# R2P_GW_module.net
KiCad netlist of a schematic drawn in EAGLE
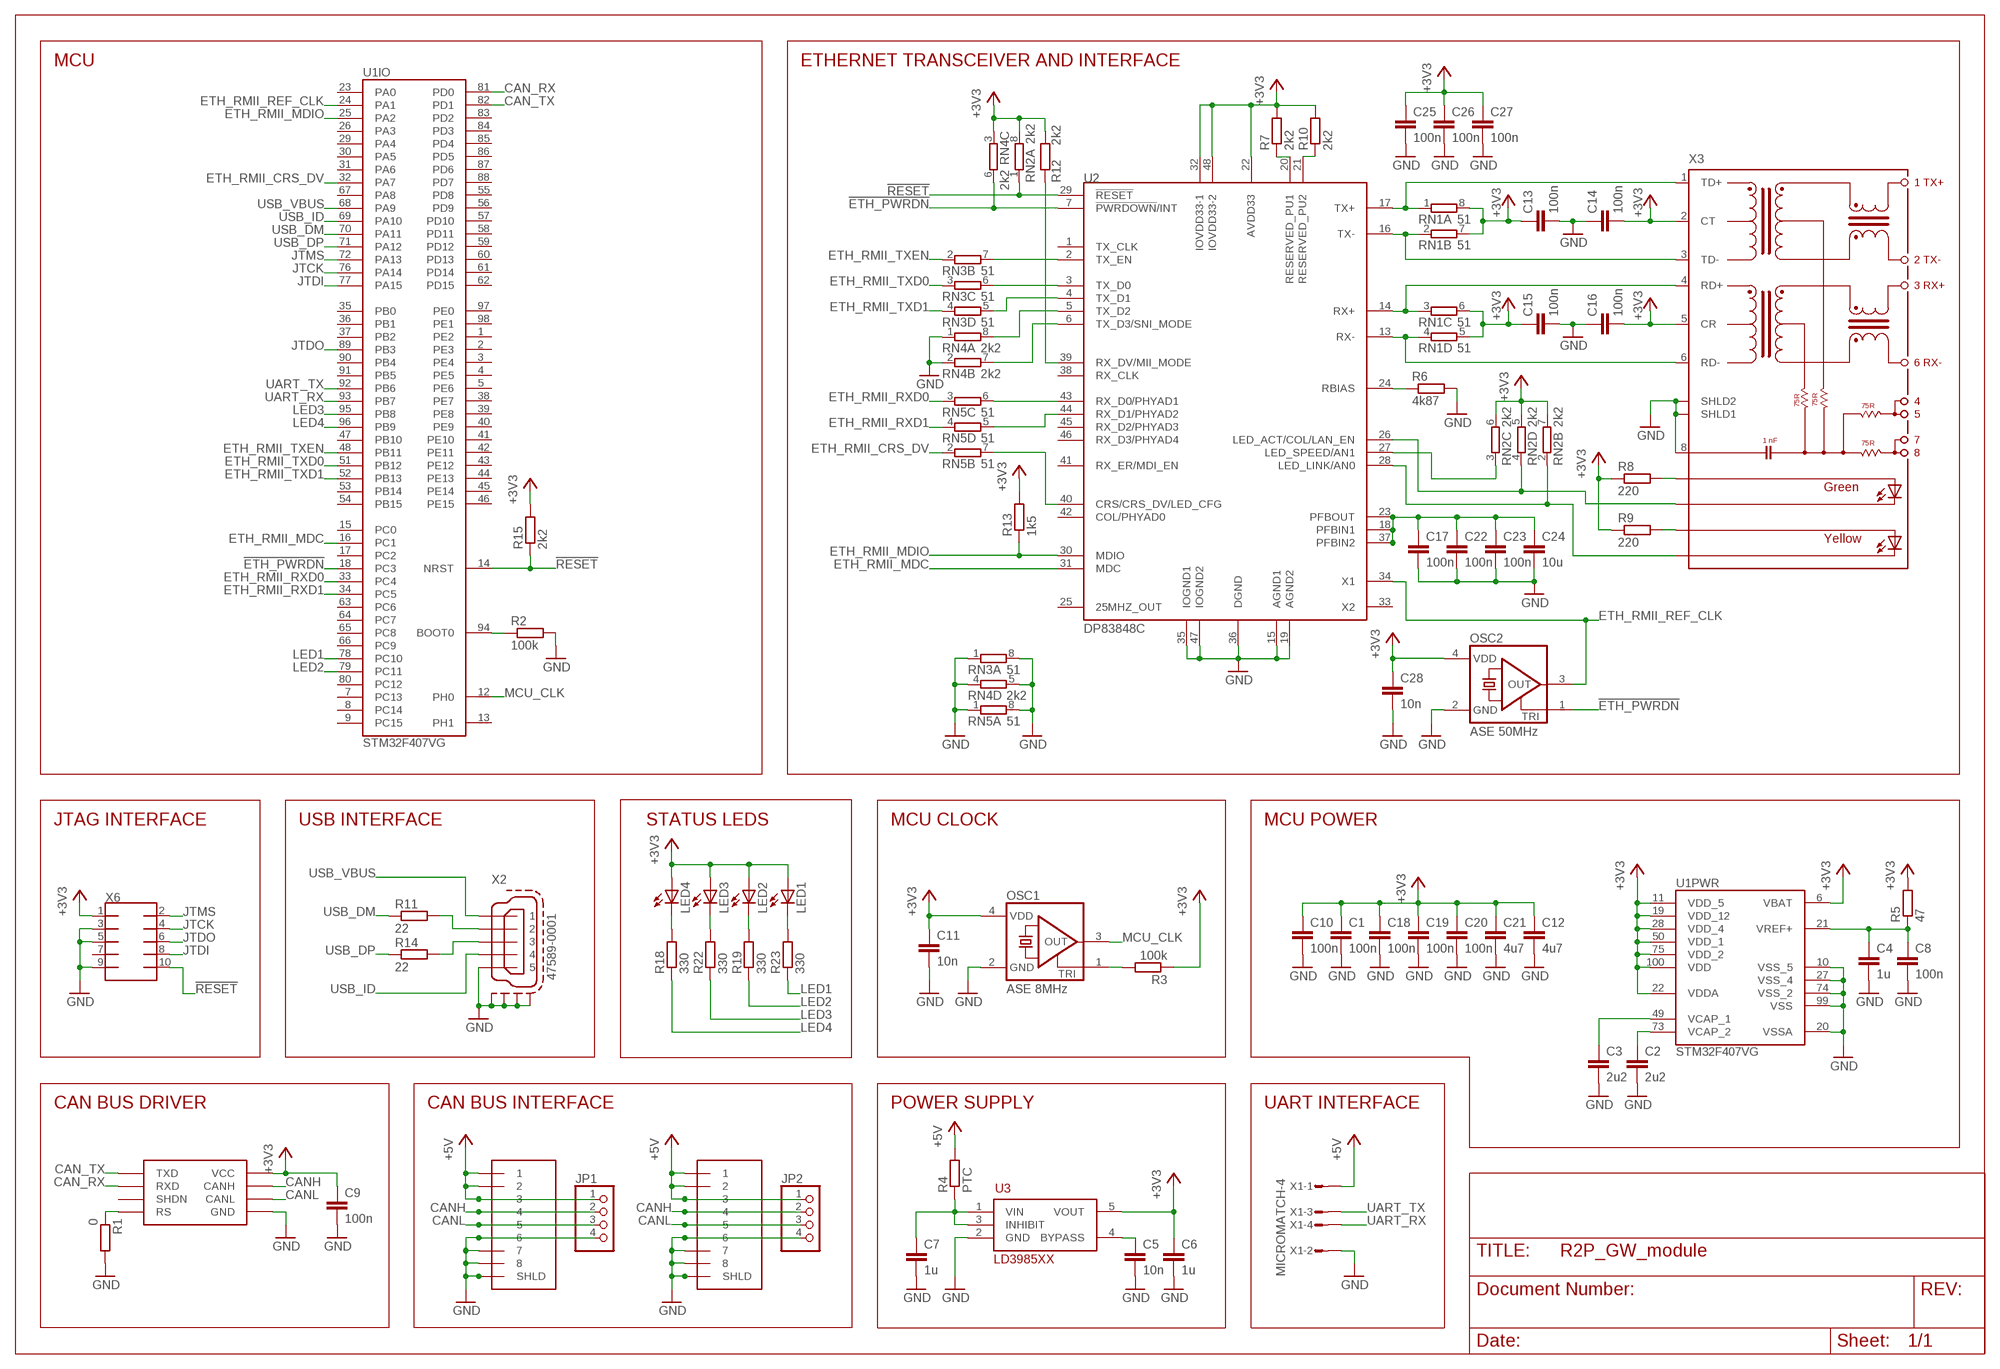
[diagram p0: schematic, sheet 1]

(export (version "E")
  (design (tool "Eeschema 10.0.6"))
  (components
    (comp (ref "C1")
      (value "100n")
      (footprint "eagle-import:C0603")
      (libsource (lib "eagle-import") (part "C-EUC0603"))
    )
    (comp (ref "C2")
      (value "2u2")
      (footprint "eagle-import:C0805")
      (libsource (lib "eagle-import") (part "C-EUC0805"))
    )
    (comp (ref "C3")
      (value "2u2")
      (footprint "eagle-import:C0805")
      (libsource (lib "eagle-import") (part "C-EUC0805"))
    )
    (comp (ref "C4")
      (value "1u")
      (footprint "eagle-import:C0603")
      (libsource (lib "eagle-import") (part "C-EUC0603"))
    )
    (comp (ref "C5")
      (value "10n")
      (footprint "eagle-import:C0603")
      (libsource (lib "eagle-import") (part "C-EUC0603"))
    )
    (comp (ref "C6")
      (value "1u")
      (footprint "eagle-import:C0603")
      (libsource (lib "eagle-import") (part "C-EUC0603"))
    )
    (comp (ref "C7")
      (value "1u")
      (footprint "eagle-import:C0603")
      (libsource (lib "eagle-import") (part "C-EUC0603"))
    )
    (comp (ref "C8")
      (value "100n")
      (footprint "eagle-import:C0603")
      (libsource (lib "eagle-import") (part "C-EUC0603"))
    )
    (comp (ref "C9")
      (value "100n")
      (footprint "eagle-import:C0603")
      (libsource (lib "eagle-import") (part "C-EUC0603"))
    )
    (comp (ref "C10")
      (value "100n")
      (footprint "eagle-import:C0603")
      (libsource (lib "eagle-import") (part "C-EUC0603"))
    )
    (comp (ref "C11")
      (value "10n")
      (footprint "eagle-import:C0603")
      (libsource (lib "eagle-import") (part "C-EUC0603"))
    )
    (comp (ref "C12")
      (value "4u7")
      (footprint "eagle-import:C0805")
      (libsource (lib "eagle-import") (part "C-EUC0805"))
    )
    (comp (ref "C13")
      (value "100n")
      (footprint "eagle-import:C0603")
      (libsource (lib "eagle-import") (part "C-EUC0603"))
    )
    (comp (ref "C14")
      (value "100n")
      (footprint "eagle-import:C0603")
      (libsource (lib "eagle-import") (part "C-EUC0603"))
    )
    (comp (ref "C15")
      (value "100n")
      (footprint "eagle-import:C0603")
      (libsource (lib "eagle-import") (part "C-EUC0603"))
    )
    (comp (ref "C16")
      (value "100n")
      (footprint "eagle-import:C0603")
      (libsource (lib "eagle-import") (part "C-EUC0603"))
    )
    (comp (ref "C17")
      (value "100n")
      (footprint "eagle-import:C0603")
      (libsource (lib "eagle-import") (part "C-EUC0603"))
    )
    (comp (ref "C18")
      (value "100n")
      (footprint "eagle-import:C0603")
      (libsource (lib "eagle-import") (part "C-EUC0603"))
    )
    (comp (ref "C19")
      (value "100n")
      (footprint "eagle-import:C0603")
      (libsource (lib "eagle-import") (part "C-EUC0603"))
    )
    (comp (ref "C20")
      (value "100n")
      (footprint "eagle-import:C0603")
      (libsource (lib "eagle-import") (part "C-EUC0603"))
    )
    (comp (ref "C21")
      (value "4u7")
      (footprint "eagle-import:C0805")
      (libsource (lib "eagle-import") (part "C-EUC0805"))
    )
    (comp (ref "C22")
      (value "100n")
      (footprint "eagle-import:C0603")
      (libsource (lib "eagle-import") (part "C-EUC0603"))
    )
    (comp (ref "C23")
      (value "100n")
      (footprint "eagle-import:C0603")
      (libsource (lib "eagle-import") (part "C-EUC0603"))
    )
    (comp (ref "C24")
      (value "10u")
      (footprint "eagle-import:C0805")
      (libsource (lib "eagle-import") (part "C-EUC0805"))
    )
    (comp (ref "C25")
      (value "100n")
      (footprint "eagle-import:C0603")
      (libsource (lib "eagle-import") (part "C-EUC0603"))
    )
    (comp (ref "C26")
      (value "100n")
      (footprint "eagle-import:C0603")
      (libsource (lib "eagle-import") (part "C-EUC0603"))
    )
    (comp (ref "C27")
      (value "100n")
      (footprint "eagle-import:C0603")
      (libsource (lib "eagle-import") (part "C-EUC0603"))
    )
    (comp (ref "C28")
      (value "10n")
      (footprint "eagle-import:C0603")
      (libsource (lib "eagle-import") (part "C-EUC0603"))
    )
    (comp (ref "JP1")
      (value "PINHD-1X4")
      (footprint "eagle-import:1X04")
      (libsource (lib "eagle-import") (part "PINHD-1X4"))
    )
    (comp (ref "JP2")
      (value "PINHD-1X4")
      (footprint "eagle-import:1X04")
      (libsource (lib "eagle-import") (part "PINHD-1X4"))
    )
    (comp (ref "LED1")
      (value "LEDCHIPLED_0805")
      (footprint "eagle-import:CHIPLED_0805")
      (libsource (lib "eagle-import") (part "LEDCHIPLED_0805"))
    )
    (comp (ref "LED2")
      (value "LEDCHIPLED_0805")
      (footprint "eagle-import:CHIPLED_0805")
      (libsource (lib "eagle-import") (part "LEDCHIPLED_0805"))
    )
    (comp (ref "LED3")
      (value "LEDCHIPLED_0805")
      (footprint "eagle-import:CHIPLED_0805")
      (libsource (lib "eagle-import") (part "LEDCHIPLED_0805"))
    )
    (comp (ref "LED4")
      (value "LEDCHIPLED_0805")
      (footprint "eagle-import:CHIPLED_0805")
      (libsource (lib "eagle-import") (part "LEDCHIPLED_0805"))
    )
    (comp (ref "OSC1")
      (value "ASE 8MHz")
      (footprint "eagle-import:ASE")
      (fields (field (name "OC_FARNELL") "unknown") (field (name "OC_NEWARK") "unknown"))
      (libsource (lib "eagle-import") (part "ASE"))
    )
    (comp (ref "OSC2")
      (value "ASE 50MHz")
      (footprint "eagle-import:ASE")
      (libsource (lib "eagle-import") (part "ASE"))
    )
    (comp (ref "R1")
      (value "0")
      (footprint "eagle-import:R0603")
      (libsource (lib "eagle-import") (part "R-EU_R0603"))
    )
    (comp (ref "R2")
      (value "100k")
      (footprint "eagle-import:R0603")
      (libsource (lib "eagle-import") (part "R-EU_R0603"))
    )
    (comp (ref "R3")
      (value "100k")
      (footprint "eagle-import:R0603")
      (libsource (lib "eagle-import") (part "R-EU_R0603"))
    )
    (comp (ref "R4")
      (value "PTC")
      (footprint "eagle-import:R0603")
      (libsource (lib "eagle-import") (part "R-EU_R0603"))
    )
    (comp (ref "R5")
      (value "47")
      (footprint "eagle-import:R0603")
      (libsource (lib "eagle-import") (part "R-EU_R0603"))
    )
    (comp (ref "R6")
      (value "4k87")
      (footprint "eagle-import:R0603")
      (libsource (lib "eagle-import") (part "R-EU_R0603"))
    )
    (comp (ref "R7")
      (value "2k2")
      (footprint "eagle-import:R0603")
      (libsource (lib "eagle-import") (part "R-EU_R0603"))
    )
    (comp (ref "R8")
      (value "220")
      (footprint "eagle-import:R0603")
      (libsource (lib "eagle-import") (part "R-EU_R0603"))
    )
    (comp (ref "R9")
      (value "220")
      (footprint "eagle-import:R0603")
      (libsource (lib "eagle-import") (part "R-EU_R0603"))
    )
    (comp (ref "R10")
      (value "2k2")
      (footprint "eagle-import:R0603")
      (libsource (lib "eagle-import") (part "R-EU_R0603"))
    )
    (comp (ref "R11")
      (value "22")
      (footprint "eagle-import:R0603")
      (libsource (lib "eagle-import") (part "R-EU_R0603"))
    )
    (comp (ref "R12")
      (value "2k2")
      (footprint "eagle-import:R0603")
      (libsource (lib "eagle-import") (part "R-EU_R0603"))
    )
    (comp (ref "R13")
      (value "1k5")
      (footprint "eagle-import:R0603")
      (libsource (lib "eagle-import") (part "R-EU_R0603"))
    )
    (comp (ref "R14")
      (value "22")
      (footprint "eagle-import:R0603")
      (libsource (lib "eagle-import") (part "R-EU_R0603"))
    )
    (comp (ref "R15")
      (value "2k2")
      (footprint "eagle-import:R0603")
      (libsource (lib "eagle-import") (part "R-EU_R0603"))
    )
    (comp (ref "R18")
      (value "330")
      (footprint "eagle-import:R0603")
      (libsource (lib "eagle-import") (part "R-EU_R0603"))
    )
    (comp (ref "R19")
      (value "330")
      (footprint "eagle-import:R0603")
      (libsource (lib "eagle-import") (part "R-EU_R0603"))
    )
    (comp (ref "R22")
      (value "330")
      (footprint "eagle-import:R0603")
      (libsource (lib "eagle-import") (part "R-EU_R0603"))
    )
    (comp (ref "R23")
      (value "330")
      (footprint "eagle-import:R0603")
      (libsource (lib "eagle-import") (part "R-EU_R0603"))
    )
    (comp (ref "RN1")
      (value "51")
      (footprint "eagle-import:CAT16")
      (libsource (lib "eagle-import") (part "4R-NCAT16"))
    )
    (comp (ref "RN2")
      (value "2k2")
      (footprint "eagle-import:CAT16")
      (libsource (lib "eagle-import") (part "4R-NCAT16"))
    )
    (comp (ref "RN3")
      (value "51")
      (footprint "eagle-import:CAT16")
      (libsource (lib "eagle-import") (part "4R-NCAT16"))
    )
    (comp (ref "RN4")
      (value "2k2")
      (footprint "eagle-import:CAT16")
      (libsource (lib "eagle-import") (part "4R-NCAT16"))
    )
    (comp (ref "RN5")
      (value "51")
      (footprint "eagle-import:CAT16")
      (libsource (lib "eagle-import") (part "4R-NCAT16"))
    )
    (comp (ref "U1")
      (value "STM32F407VG")
      (footprint "eagle-import:LQFP100")
      (libsource (lib "eagle-import") (part "STM32F407VG"))
    )
    (comp (ref "U2")
      (value "DP83848C")
      (footprint "eagle-import:LQFP48")
      (libsource (lib "eagle-import") (part "DP83848C"))
    )
    (comp (ref "U3")
      (value "LD3985XX")
      (footprint "eagle-import:SOT23-5L")
      (libsource (lib "eagle-import") (part "LD3985XX"))
    )
    (comp (ref "U4")
      (value "MAX3051")
      (footprint "eagle-import:SOT23-8L")
      (libsource (lib "eagle-import") (part "MAX3051"))
    )
    (comp (ref "X1")
      (value "MICROMATCH-4")
      (footprint "eagle-import:MICROMATCH-4")
      (libsource (lib "eagle-import") (part "MICROMATCH-4"))
    )
    (comp (ref "X2")
      (value "47589-0001")
      (footprint "eagle-import:47589-0001")
      (libsource (lib "eagle-import") (part "47589-0001"))
    )
    (comp (ref "X3")
      (value "SI-60062-F")
      (footprint "eagle-import:SI-60062-F")
      (libsource (lib "eagle-import") (part "SI-60062-F"))
    )
    (comp (ref "X4")
      (value "RJ45-43860")
      (footprint "eagle-import:0438600010")
      (libsource (lib "eagle-import") (part "RJ45-43860"))
    )
    (comp (ref "X5")
      (value "RJ45-43860")
      (footprint "eagle-import:0438600010")
      (libsource (lib "eagle-import") (part "RJ45-43860"))
    )
    (comp (ref "X6")
      (value "FTSH-105")
      (footprint "eagle-import:FTSH-105")
      (libsource (lib "eagle-import") (part "FTSH-105"))
    )
  )
  (nets
    (net (code "1") (name "+3V3") (class "Default")
      (node (ref "C1") (pin "1") (pinfunction "1_1") (pintype "passive"))
      (node (ref "C10") (pin "1") (pinfunction "1_1") (pintype "passive"))
      (node (ref "C11") (pin "1") (pinfunction "1_1") (pintype "passive"))
      (node (ref "C12") (pin "1") (pinfunction "1_1") (pintype "passive"))
      (node (ref "C13") (pin "1") (pinfunction "1_1") (pintype "passive"))
      (node (ref "C14") (pin "2") (pinfunction "2_2") (pintype "passive"))
      (node (ref "C15") (pin "1") (pinfunction "1_1") (pintype "passive"))
      (node (ref "C16") (pin "2") (pinfunction "2_2") (pintype "passive"))
      (node (ref "C18") (pin "1") (pinfunction "1_1") (pintype "passive"))
      (node (ref "C19") (pin "1") (pinfunction "1_1") (pintype "passive"))
      (node (ref "C20") (pin "1") (pinfunction "1_1") (pintype "passive"))
      (node (ref "C21") (pin "1") (pinfunction "1_1") (pintype "passive"))
      (node (ref "C25") (pin "1") (pinfunction "1_1") (pintype "passive"))
      (node (ref "C26") (pin "1") (pinfunction "1_1") (pintype "passive"))
      (node (ref "C27") (pin "1") (pinfunction "1_1") (pintype "passive"))
      (node (ref "C28") (pin "1") (pinfunction "1_1") (pintype "passive"))
      (node (ref "C6") (pin "1") (pinfunction "1_1") (pintype "passive"))
      (node (ref "C9") (pin "1") (pinfunction "1_1") (pintype "passive"))
      (node (ref "LED1") (pin "A") (pinfunction "A_A") (pintype "passive"))
      (node (ref "LED2") (pin "A") (pinfunction "A_A") (pintype "passive"))
      (node (ref "LED3") (pin "A") (pinfunction "A_A") (pintype "passive"))
      (node (ref "LED4") (pin "A") (pinfunction "A_A") (pintype "passive"))
      (node (ref "OSC1") (pin "4") (pinfunction "VDD_4") (pintype "power_in"))
      (node (ref "OSC2") (pin "4") (pinfunction "VDD_4") (pintype "power_in"))
      (node (ref "R10") (pin "2") (pinfunction "2_2") (pintype "passive"))
      (node (ref "R12") (pin "2") (pinfunction "2_2") (pintype "passive"))
      (node (ref "R13") (pin "2") (pinfunction "2_2") (pintype "passive"))
      (node (ref "R15") (pin "2") (pinfunction "2_2") (pintype "passive"))
      (node (ref "R3") (pin "1") (pinfunction "1_1") (pintype "passive"))
      (node (ref "R5") (pin "2") (pinfunction "2_2") (pintype "passive"))
      (node (ref "R7") (pin "2") (pinfunction "2_2") (pintype "passive"))
      (node (ref "R8") (pin "1") (pinfunction "1_1") (pintype "passive"))
      (node (ref "R9") (pin "1") (pinfunction "1_1") (pintype "passive"))
      (node (ref "RN1") (pin "5") (pinfunction "2_5") (pintype "passive"))
      (node (ref "RN1") (pin "6") (pinfunction "2_6") (pintype "passive"))
      (node (ref "RN1") (pin "7") (pinfunction "2_7") (pintype "passive"))
      (node (ref "RN1") (pin "8") (pinfunction "2_8") (pintype "passive"))
      (node (ref "RN2") (pin "5") (pinfunction "2_5") (pintype "passive"))
      (node (ref "RN2") (pin "6") (pinfunction "2_6") (pintype "passive"))
      (node (ref "RN2") (pin "7") (pinfunction "2_7") (pintype "passive"))
      (node (ref "RN2") (pin "8") (pinfunction "2_8") (pintype "passive"))
      (node (ref "RN4") (pin "3") (pinfunction "1_3") (pintype "passive"))
      (node (ref "U1") (pin "100") (pinfunction "VDD_100") (pintype "power_in"))
      (node (ref "U1") (pin "11") (pinfunction "VDD_5_11") (pintype "power_in"))
      (node (ref "U1") (pin "19") (pinfunction "VDD_12_19") (pintype "power_in"))
      (node (ref "U1") (pin "22") (pinfunction "VDDA_22") (pintype "power_in"))
      (node (ref "U1") (pin "28") (pinfunction "VDD_4_28") (pintype "power_in"))
      (node (ref "U1") (pin "50") (pinfunction "VDD_1_50") (pintype "power_in"))
      (node (ref "U1") (pin "6") (pinfunction "VBAT_6") (pintype "power_in"))
      (node (ref "U1") (pin "75") (pinfunction "VDD_2_75") (pintype "power_in"))
      (node (ref "U2") (pin "22") (pinfunction "AVDD33_22") (pintype "bidirectional"))
      (node (ref "U2") (pin "32") (pinfunction "IOVDD33-1_32") (pintype "bidirectional"))
      (node (ref "U2") (pin "48") (pinfunction "IOVDD33-2_48") (pintype "bidirectional"))
      (node (ref "U3") (pin "5") (pinfunction "VOUT_5") (pintype "bidirectional"))
      (node (ref "U4") (pin "P$3") (pinfunction "VCC_P$3") (pintype "bidirectional"))
      (node (ref "X3") (pin "2") (pinfunction "CT_2") (pintype "passive"))
      (node (ref "X3") (pin "5") (pinfunction "CR_5") (pintype "passive"))
      (node (ref "X6") (pin "1") (pinfunction "1_1") (pintype "passive"))
    )
    (net (code "2") (name "+5V") (class "Default")
      (node (ref "JP1") (pin "1") (pinfunction "1_1") (pintype "passive"))
      (node (ref "JP2") (pin "1") (pinfunction "1_1") (pintype "passive"))
      (node (ref "R4") (pin "2") (pinfunction "2_2") (pintype "passive"))
      (node (ref "X1") (pin "1") (pinfunction "S_1") (pintype "passive"))
      (node (ref "X4") (pin "P$1") (pinfunction "1_P$1") (pintype "bidirectional"))
      (node (ref "X4") (pin "P$2") (pinfunction "2_P$2") (pintype "bidirectional"))
      (node (ref "X4") (pin "P$3") (pinfunction "3_P$3") (pintype "bidirectional"))
      (node (ref "X5") (pin "P$1") (pinfunction "1_P$1") (pintype "bidirectional"))
      (node (ref "X5") (pin "P$2") (pinfunction "2_P$2") (pintype "bidirectional"))
      (node (ref "X5") (pin "P$3") (pinfunction "3_P$3") (pintype "bidirectional"))
    )
    (net (code "3") (name "/CANH") (class "Default")
      (node (ref "JP1") (pin "2") (pinfunction "2_2") (pintype "passive"))
      (node (ref "JP2") (pin "2") (pinfunction "2_2") (pintype "passive"))
      (node (ref "U4") (pin "P$7") (pinfunction "CANH_P$7") (pintype "bidirectional"))
      (node (ref "X4") (pin "P$4") (pinfunction "4_P$4") (pintype "bidirectional"))
      (node (ref "X5") (pin "P$4") (pinfunction "4_P$4") (pintype "bidirectional"))
    )
    (net (code "4") (name "/CANL") (class "Default")
      (node (ref "JP1") (pin "3") (pinfunction "3_3") (pintype "passive"))
      (node (ref "JP2") (pin "3") (pinfunction "3_3") (pintype "passive"))
      (node (ref "U4") (pin "P$6") (pinfunction "CANL_P$6") (pintype "bidirectional"))
      (node (ref "X4") (pin "P$5") (pinfunction "5_P$5") (pintype "bidirectional"))
      (node (ref "X5") (pin "P$5") (pinfunction "5_P$5") (pintype "bidirectional"))
    )
    (net (code "5") (name "/CAN_RX") (class "Default")
      (node (ref "U1") (pin "81") (pinfunction "PD0_81") (pintype "passive"))
      (node (ref "U4") (pin "P$4") (pinfunction "RXD_P$4") (pintype "bidirectional"))
    )
    (net (code "6") (name "/CAN_TX") (class "Default")
      (node (ref "U1") (pin "82") (pinfunction "PD1_82") (pintype "passive"))
      (node (ref "U4") (pin "P$1") (pinfunction "TXD_P$1") (pintype "bidirectional"))
    )
    (net (code "7") (name "/ETH_RMII_CRS_DV") (class "Default")
      (node (ref "RN5") (pin "2") (pinfunction "1_2") (pintype "passive"))
      (node (ref "U1") (pin "32") (pinfunction "PA7_32") (pintype "passive"))
    )
    (net (code "8") (name "/ETH_RMII_MDC") (class "Default")
      (node (ref "U1") (pin "16") (pinfunction "PC1_16") (pintype "passive"))
      (node (ref "U2") (pin "31") (pinfunction "MDC_31") (pintype "bidirectional"))
    )
    (net (code "9") (name "/ETH_RMII_MDIO") (class "Default")
      (node (ref "R13") (pin "1") (pinfunction "1_1") (pintype "passive"))
      (node (ref "U1") (pin "25") (pinfunction "PA2_25") (pintype "passive"))
      (node (ref "U2") (pin "30") (pinfunction "MDIO_30") (pintype "bidirectional"))
    )
    (net (code "10") (name "/ETH_RMII_REF_CLK") (class "Default")
      (node (ref "OSC2") (pin "3") (pinfunction "OUT_3") (pintype "output"))
      (node (ref "U1") (pin "24") (pinfunction "PA1_24") (pintype "passive"))
      (node (ref "U2") (pin "34") (pinfunction "X1_34") (pintype "bidirectional"))
    )
    (net (code "11") (name "/ETH_RMII_RXD0") (class "Default")
      (node (ref "RN5") (pin "3") (pinfunction "1_3") (pintype "passive"))
      (node (ref "U1") (pin "33") (pinfunction "PC4_33") (pintype "passive"))
    )
    (net (code "12") (name "/ETH_RMII_RXD1") (class "Default")
      (node (ref "RN5") (pin "4") (pinfunction "1_4") (pintype "passive"))
      (node (ref "U1") (pin "34") (pinfunction "PC5_34") (pintype "passive"))
    )
    (net (code "13") (name "/ETH_RMII_TXD0") (class "Default")
      (node (ref "RN3") (pin "3") (pinfunction "1_3") (pintype "passive"))
      (node (ref "U1") (pin "51") (pinfunction "PB12_51") (pintype "passive"))
    )
    (net (code "14") (name "/ETH_RMII_TXD1") (class "Default")
      (node (ref "RN3") (pin "4") (pinfunction "1_4") (pintype "passive"))
      (node (ref "U1") (pin "52") (pinfunction "PB13_52") (pintype "passive"))
    )
    (net (code "15") (name "/ETH_RMII_TXEN") (class "Default")
      (node (ref "RN3") (pin "2") (pinfunction "1_2") (pintype "passive"))
      (node (ref "U1") (pin "48") (pinfunction "PB11_48") (pintype "passive"))
    )
    (net (code "16") (name "/JTCK") (class "Default")
      (node (ref "U1") (pin "76") (pinfunction "PA14_76") (pintype "passive"))
      (node (ref "X6") (pin "4") (pinfunction "4_4") (pintype "passive"))
    )
    (net (code "17") (name "/JTDI") (class "Default")
      (node (ref "U1") (pin "77") (pinfunction "PA15_77") (pintype "passive"))
      (node (ref "X6") (pin "8") (pinfunction "8_8") (pintype "passive"))
    )
    (net (code "18") (name "/JTDO") (class "Default")
      (node (ref "U1") (pin "89") (pinfunction "PB3_89") (pintype "passive"))
      (node (ref "X6") (pin "6") (pinfunction "6_6") (pintype "passive"))
    )
    (net (code "19") (name "/JTMS") (class "Default")
      (node (ref "U1") (pin "72") (pinfunction "PA13_72") (pintype "passive"))
      (node (ref "X6") (pin "2") (pinfunction "2_2") (pintype "passive"))
    )
    (net (code "20") (name "/LED1") (class "Default")
      (node (ref "R23") (pin "1") (pinfunction "1_1") (pintype "passive"))
      (node (ref "U1") (pin "78") (pinfunction "PC10_78") (pintype "passive"))
    )
    (net (code "21") (name "/LED2") (class "Default")
      (node (ref "R19") (pin "1") (pinfunction "1_1") (pintype "passive"))
      (node (ref "U1") (pin "79") (pinfunction "PC11_79") (pintype "passive"))
    )
    (net (code "22") (name "/LED3") (class "Default")
      (node (ref "R22") (pin "1") (pinfunction "1_1") (pintype "passive"))
      (node (ref "U1") (pin "95") (pinfunction "PB8_95") (pintype "passive"))
    )
    (net (code "23") (name "/LED4") (class "Default")
      (node (ref "R18") (pin "1") (pinfunction "1_1") (pintype "passive"))
      (node (ref "U1") (pin "96") (pinfunction "PB9_96") (pintype "passive"))
    )
    (net (code "24") (name "/MCU_CLK") (class "Default")
      (node (ref "OSC1") (pin "3") (pinfunction "OUT_3") (pintype "output"))
      (node (ref "U1") (pin "12") (pinfunction "PH0_12") (pintype "passive"))
    )
    (net (code "25") (name "/UART_RX") (class "Default")
      (node (ref "U1") (pin "93") (pinfunction "PB7_93") (pintype "passive"))
      (node (ref "X1") (pin "4") (pinfunction "S_4") (pintype "passive"))
    )
    (net (code "26") (name "/UART_TX") (class "Default")
      (node (ref "U1") (pin "92") (pinfunction "PB6_92") (pintype "passive"))
      (node (ref "X1") (pin "3") (pinfunction "S_3") (pintype "passive"))
    )
    (net (code "27") (name "/USB_DM") (class "Default")
      (node (ref "R11") (pin "1") (pinfunction "1_1") (pintype "passive"))
      (node (ref "U1") (pin "70") (pinfunction "PA11_70") (pintype "passive"))
    )
    (net (code "28") (name "/USB_DP") (class "Default")
      (node (ref "R14") (pin "1") (pinfunction "1_1") (pintype "passive"))
      (node (ref "U1") (pin "71") (pinfunction "PA12_71") (pintype "passive"))
    )
    (net (code "29") (name "/USB_ID") (class "Default")
      (node (ref "U1") (pin "69") (pinfunction "PA10_69") (pintype "passive"))
      (node (ref "X2") (pin "4") (pinfunction "4_4") (pintype "passive"))
    )
    (net (code "30") (name "/USB_VBUS") (class "Default")
      (node (ref "U1") (pin "68") (pinfunction "PA9_68") (pintype "passive"))
      (node (ref "X2") (pin "1") (pinfunction "1_1") (pintype "passive"))
    )
    (net (code "31") (name "/~{ETH_PWRDN}") (class "Default")
      (node (ref "OSC2") (pin "1") (pinfunction "TRI_1") (pintype "input"))
      (node (ref "RN4") (pin "6") (pinfunction "2_6") (pintype "passive"))
      (node (ref "U1") (pin "18") (pinfunction "PC3_18") (pintype "passive"))
      (node (ref "U2") (pin "7") (pinfunction "~{PWRDOWN}/INT_7") (pintype "bidirectional"))
    )
    (net (code "32") (name "/~{RESET}") (class "Default")
      (node (ref "R15") (pin "1") (pinfunction "1_1") (pintype "passive"))
      (node (ref "RN2") (pin "1") (pinfunction "1_1") (pintype "passive"))
      (node (ref "U1") (pin "14") (pinfunction "NRST_14") (pintype "passive"))
      (node (ref "U2") (pin "29") (pinfunction "~{RESET}_29") (pintype "bidirectional"))
      (node (ref "X6") (pin "10") (pinfunction "10_10") (pintype "passive"))
    )
    (net (code "33") (name "GND") (class "Default")
      (node (ref "C1") (pin "2") (pinfunction "2_2") (pintype "passive"))
      (node (ref "C10") (pin "2") (pinfunction "2_2") (pintype "passive"))
      (node (ref "C11") (pin "2") (pinfunction "2_2") (pintype "passive"))
      (node (ref "C12") (pin "2") (pinfunction "2_2") (pintype "passive"))
      (node (ref "C13") (pin "2") (pinfunction "2_2") (pintype "passive"))
      (node (ref "C14") (pin "1") (pinfunction "1_1") (pintype "passive"))
      (node (ref "C15") (pin "2") (pinfunction "2_2") (pintype "passive"))
      (node (ref "C16") (pin "1") (pinfunction "1_1") (pintype "passive"))
      (node (ref "C17") (pin "2") (pinfunction "2_2") (pintype "passive"))
      (node (ref "C18") (pin "2") (pinfunction "2_2") (pintype "passive"))
      (node (ref "C19") (pin "2") (pinfunction "2_2") (pintype "passive"))
      (node (ref "C2") (pin "2") (pinfunction "2_2") (pintype "passive"))
      (node (ref "C20") (pin "2") (pinfunction "2_2") (pintype "passive"))
      (node (ref "C21") (pin "2") (pinfunction "2_2") (pintype "passive"))
      (node (ref "C22") (pin "2") (pinfunction "2_2") (pintype "passive"))
      (node (ref "C23") (pin "2") (pinfunction "2_2") (pintype "passive"))
      (node (ref "C24") (pin "2") (pinfunction "2_2") (pintype "passive"))
      (node (ref "C25") (pin "2") (pinfunction "2_2") (pintype "passive"))
      (node (ref "C26") (pin "2") (pinfunction "2_2") (pintype "passive"))
      (node (ref "C27") (pin "2") (pinfunction "2_2") (pintype "passive"))
      (node (ref "C28") (pin "2") (pinfunction "2_2") (pintype "passive"))
      (node (ref "C3") (pin "2") (pinfunction "2_2") (pintype "passive"))
      (node (ref "C4") (pin "2") (pinfunction "2_2") (pintype "passive"))
      (node (ref "C5") (pin "2") (pinfunction "2_2") (pintype "passive"))
      (node (ref "C6") (pin "2") (pinfunction "2_2") (pintype "passive"))
      (node (ref "C7") (pin "2") (pinfunction "2_2") (pintype "passive"))
      (node (ref "C8") (pin "2") (pinfunction "2_2") (pintype "passive"))
      (node (ref "C9") (pin "2") (pinfunction "2_2") (pintype "passive"))
      (node (ref "JP1") (pin "4") (pinfunction "4_4") (pintype "passive"))
      (node (ref "JP2") (pin "4") (pinfunction "4_4") (pintype "passive"))
      (node (ref "OSC1") (pin "2") (pinfunction "GND_2") (pintype "power_in"))
      (node (ref "OSC2") (pin "2") (pinfunction "GND_2") (pintype "power_in"))
      (node (ref "R1") (pin "2") (pinfunction "2_2") (pintype "passive"))
      (node (ref "R2") (pin "2") (pinfunction "2_2") (pintype "passive"))
      (node (ref "R6") (pin "2") (pinfunction "2_2") (pintype "passive"))
      (node (ref "RN3") (pin "1") (pinfunction "1_1") (pintype "passive"))
      (node (ref "RN3") (pin "8") (pinfunction "2_8") (pintype "passive"))
      (node (ref "RN4") (pin "1") (pinfunction "1_1") (pintype "passive"))
      (node (ref "RN4") (pin "2") (pinfunction "1_2") (pintype "passive"))
      (node (ref "RN4") (pin "4") (pinfunction "1_4") (pintype "passive"))
      (node (ref "RN4") (pin "5") (pinfunction "2_5") (pintype "passive"))
      (node (ref "RN5") (pin "1") (pinfunction "1_1") (pintype "passive"))
      (node (ref "RN5") (pin "8") (pinfunction "2_8") (pintype "passive"))
      (node (ref "U1") (pin "10") (pinfunction "VSS_5_10") (pintype "power_in"))
      (node (ref "U1") (pin "20") (pinfunction "VSSA_20") (pintype "power_in"))
      (node (ref "U1") (pin "27") (pinfunction "VSS_4_27") (pintype "power_in"))
      (node (ref "U1") (pin "74") (pinfunction "VSS_2_74") (pintype "power_in"))
      (node (ref "U1") (pin "99") (pinfunction "VSS_99") (pintype "power_in"))
      (node (ref "U2") (pin "15") (pinfunction "AGND1_15") (pintype "bidirectional"))
      (node (ref "U2") (pin "19") (pinfunction "AGND2_19") (pintype "bidirectional"))
      (node (ref "U2") (pin "35") (pinfunction "IOGND1_35") (pintype "bidirectional"))
      (node (ref "U2") (pin "36") (pinfunction "DGND_36") (pintype "bidirectional"))
      (node (ref "U2") (pin "47") (pinfunction "IOGND2_47") (pintype "bidirectional"))
      (node (ref "U3") (pin "2") (pinfunction "GND_2") (pintype "bidirectional"))
      (node (ref "U4") (pin "P$2") (pinfunction "GND_P$2") (pintype "bidirectional"))
      (node (ref "X1") (pin "2") (pinfunction "S_2") (pintype "passive"))
      (node (ref "X2") (pin "5") (pinfunction "5_5") (pintype "passive"))
      (node (ref "X2") (pin "SHLD1") (pinfunction "SHLD1_SHLD1") (pintype "passive"))
      (node (ref "X2") (pin "SHLD2") (pinfunction "SHLD2_SHLD2") (pintype "passive"))
      (node (ref "X2") (pin "SHLD3") (pinfunction "SHLD3_SHLD3") (pintype "passive"))
      (node (ref "X2") (pin "SHLD4") (pinfunction "SHLD4_SHLD4") (pintype "passive"))
      (node (ref "X3") (pin "8") (pinfunction "8_8") (pintype "passive"))
      (node (ref "X3") (pin "SHLD1") (pinfunction "SHLD1_SHLD1") (pintype "passive"))
      (node (ref "X3") (pin "SHLD2") (pinfunction "SHLD2_SHLD2") (pintype "passive"))
      (node (ref "X4") (pin "P$10") (pinfunction "P$1_P$10") (pintype "power_in"))
      (node (ref "X4") (pin "P$6") (pinfunction "6_P$6") (pintype "bidirectional"))
      (node (ref "X4") (pin "P$7") (pinfunction "7_P$7") (pintype "bidirectional"))
      (node (ref "X4") (pin "P$8") (pinfunction "8_P$8") (pintype "bidirectional"))
      (node (ref "X4") (pin "P$9") (pinfunction "SHLD_P$9") (pintype "power_in"))
      (node (ref "X5") (pin "P$10") (pinfunction "P$1_P$10") (pintype "power_in"))
      (node (ref "X5") (pin "P$6") (pinfunction "6_P$6") (pintype "bidirectional"))
      (node (ref "X5") (pin "P$7") (pinfunction "7_P$7") (pintype "bidirectional"))
      (node (ref "X5") (pin "P$8") (pinfunction "8_P$8") (pintype "bidirectional"))
      (node (ref "X5") (pin "P$9") (pinfunction "SHLD_P$9") (pintype "power_in"))
      (node (ref "X6") (pin "3") (pinfunction "3_3") (pintype "passive"))
      (node (ref "X6") (pin "5") (pinfunction "5_5") (pintype "passive"))
      (node (ref "X6") (pin "9") (pinfunction "9_9") (pintype "passive"))
    )
    (net (code "34") (name "Net-(LED1-PadC)") (class "Default")
      (node (ref "LED1") (pin "C") (pinfunction "C_C") (pintype "passive"))
      (node (ref "R23") (pin "2") (pinfunction "2_2") (pintype "passive"))
    )
    (net (code "35") (name "Net-(LED2-PadC)") (class "Default")
      (node (ref "LED2") (pin "C") (pinfunction "C_C") (pintype "passive"))
      (node (ref "R19") (pin "2") (pinfunction "2_2") (pintype "passive"))
    )
    (net (code "36") (name "Net-(LED3-PadC)") (class "Default")
      (node (ref "LED3") (pin "C") (pinfunction "C_C") (pintype "passive"))
      (node (ref "R22") (pin "2") (pinfunction "2_2") (pintype "passive"))
    )
    (net (code "37") (name "Net-(LED4-PadC)") (class "Default")
      (node (ref "LED4") (pin "C") (pinfunction "C_C") (pintype "passive"))
      (node (ref "R18") (pin "2") (pinfunction "2_2") (pintype "passive"))
    )
    (net (code "38") (name "Net-(OSC1-TRI)") (class "Default")
      (node (ref "OSC1") (pin "1") (pinfunction "TRI_1") (pintype "input"))
      (node (ref "R3") (pin "2") (pinfunction "2_2") (pintype "passive"))
    )
    (net (code "39") (name "Net-(R8-Pad2)") (class "Default")
      (node (ref "R8") (pin "2") (pinfunction "2_2") (pintype "passive"))
      (node (ref "X3") (pin "GA") (pinfunction "GA_GA") (pintype "passive"))
    )
    (net (code "40") (name "Net-(R9-Pad2)") (class "Default")
      (node (ref "R9") (pin "2") (pinfunction "2_2") (pintype "passive"))
      (node (ref "X3") (pin "YA") (pinfunction "YA_YA") (pintype "passive"))
    )
    (net (code "41") (name "Net-(R11-Pad2)") (class "Default")
      (node (ref "R11") (pin "2") (pinfunction "2_2") (pintype "passive"))
      (node (ref "X2") (pin "2") (pinfunction "2_2") (pintype "passive"))
    )
    (net (code "42") (name "Net-(R14-Pad2)") (class "Default")
      (node (ref "R14") (pin "2") (pinfunction "2_2") (pintype "passive"))
      (node (ref "X2") (pin "3") (pinfunction "3_3") (pintype "passive"))
    )
    (net (code "43") (name "Net-(RN1B-1)") (class "Default")
      (node (ref "RN1") (pin "2") (pinfunction "1_2") (pintype "passive"))
      (node (ref "U2") (pin "16") (pinfunction "TX-_16") (pintype "bidirectional"))
      (node (ref "X3") (pin "3") (pinfunction "TD-_3") (pintype "passive"))
    )
    (net (code "44") (name "Net-(RN1C-1)") (class "Default")
      (node (ref "RN1") (pin "3") (pinfunction "1_3") (pintype "passive"))
      (node (ref "U2") (pin "14") (pinfunction "RX+_14") (pintype "bidirectional"))
      (node (ref "X3") (pin "4") (pinfunction "RD+_4") (pintype "passive"))
    )
    (net (code "45") (name "Net-(RN1D-1)") (class "Default")
      (node (ref "RN1") (pin "4") (pinfunction "1_4") (pintype "passive"))
      (node (ref "U2") (pin "13") (pinfunction "RX-_13") (pintype "bidirectional"))
      (node (ref "X3") (pin "6") (pinfunction "RD-_6") (pintype "passive"))
    )
    (net (code "46") (name "Net-(RN2B-1)") (class "Default")
      (node (ref "RN2") (pin "2") (pinfunction "1_2") (pintype "passive"))
      (node (ref "U2") (pin "28") (pinfunction "LED_LINK/AN0_28") (pintype "bidirectional"))
      (node (ref "X3") (pin "YK") (pinfunction "YK_YK") (pintype "passive"))
    )
    (net (code "47") (name "Net-(RN2C-1)") (class "Default")
      (node (ref "RN2") (pin "3") (pinfunction "1_3") (pintype "passive"))
      (node (ref "U2") (pin "27") (pinfunction "LED_SPEED/AN1_27") (pintype "bidirectional"))
    )
    (net (code "48") (name "Net-(RN2D-1)") (class "Default")
      (node (ref "RN2") (pin "4") (pinfunction "1_4") (pintype "passive"))
      (node (ref "U2") (pin "26") (pinfunction "LED_ACT/COL/LAN_EN_26") (pintype "bidirectional"))
      (node (ref "X3") (pin "GK") (pinfunction "GK_GK") (pintype "passive"))
    )
    (net (code "49") (name "Net-(RN3B-2)") (class "Default")
      (node (ref "RN3") (pin "7") (pinfunction "2_7") (pintype "passive"))
      (node (ref "U2") (pin "2") (pinfunction "TX_EN_2") (pintype "bidirectional"))
    )
    (net (code "50") (name "Net-(RN3C-2)") (class "Default")
      (node (ref "RN3") (pin "6") (pinfunction "2_6") (pintype "passive"))
      (node (ref "U2") (pin "3") (pinfunction "TX_D0_3") (pintype "bidirectional"))
    )
    (net (code "51") (name "Net-(RN3D-2)") (class "Default")
      (node (ref "RN3") (pin "5") (pinfunction "2_5") (pintype "passive"))
      (node (ref "U2") (pin "4") (pinfunction "TX_D1_4") (pintype "bidirectional"))
    )
    (net (code "52") (name "Net-(RN4A-2)") (class "Default")
      (node (ref "RN4") (pin "8") (pinfunction "2_8") (pintype "passive"))
      (node (ref "U2") (pin "5") (pinfunction "TX_D2_5") (pintype "bidirectional"))
    )
    (net (code "53") (name "Net-(RN4B-2)") (class "Default")
      (node (ref "RN4") (pin "7") (pinfunction "2_7") (pintype "passive"))
      (node (ref "U2") (pin "6") (pinfunction "TX_D3/SNI_MODE_6") (pintype "bidirectional"))
    )
    (net (code "54") (name "Net-(RN5B-2)") (class "Default")
      (node (ref "RN5") (pin "7") (pinfunction "2_7") (pintype "passive"))
      (node (ref "U2") (pin "40") (pinfunction "CRS/CRS_DV/LED_CFG_40") (pintype "bidirectional"))
    )
    (net (code "55") (name "Net-(RN5C-2)") (class "Default")
      (node (ref "RN5") (pin "6") (pinfunction "2_6") (pintype "passive"))
      (node (ref "U2") (pin "43") (pinfunction "RX_D0/PHYAD1_43") (pintype "bidirectional"))
    )
    (net (code "56") (name "Net-(RN5D-2)") (class "Default")
      (node (ref "RN5") (pin "5") (pinfunction "2_5") (pintype "passive"))
      (node (ref "U2") (pin "44") (pinfunction "RX_D1/PHYAD2_44") (pintype "bidirectional"))
    )
    (net (code "57") (name "Net-(U1A-BOOT0)") (class "Default")
      (node (ref "R2") (pin "1") (pinfunction "1_1") (pintype "passive"))
      (node (ref "U1") (pin "94") (pinfunction "BOOT0_94") (pintype "passive"))
    )
    (net (code "58") (name "Net-(U1B-VCAP_1)") (class "Default")
      (node (ref "C3") (pin "1") (pinfunction "1_1") (pintype "passive"))
      (node (ref "U1") (pin "49") (pinfunction "VCAP_1_49") (pintype "power_in"))
    )
    (net (code "59") (name "Net-(U1B-VCAP_2)") (class "Default")
      (node (ref "C2") (pin "1") (pinfunction "1_1") (pintype "passive"))
      (node (ref "U1") (pin "73") (pinfunction "VCAP_2_73") (pintype "power_in"))
    )
    (net (code "60") (name "Net-(U1B-VREF+)") (class "Default")
      (node (ref "C4") (pin "1") (pinfunction "1_1") (pintype "passive"))
      (node (ref "C8") (pin "1") (pinfunction "1_1") (pintype "passive"))
      (node (ref "R5") (pin "1") (pinfunction "1_1") (pintype "passive"))
      (node (ref "U1") (pin "21") (pinfunction "VREF+_21") (pintype "passive"))
    )
    (net (code "61") (name "Net-(U2-PFBIN1)") (class "Default")
      (node (ref "C17") (pin "1") (pinfunction "1_1") (pintype "passive"))
      (node (ref "C22") (pin "1") (pinfunction "1_1") (pintype "passive"))
      (node (ref "C23") (pin "1") (pinfunction "1_1") (pintype "passive"))
      (node (ref "C24") (pin "1") (pinfunction "1_1") (pintype "passive"))
      (node (ref "U2") (pin "18") (pinfunction "PFBIN1_18") (pintype "bidirectional"))
      (node (ref "U2") (pin "23") (pinfunction "PFBOUT_23") (pintype "bidirectional"))
      (node (ref "U2") (pin "37") (pinfunction "PFBIN2_37") (pintype "bidirectional"))
    )
    (net (code "62") (name "Net-(U2-RBIAS)") (class "Default")
      (node (ref "R6") (pin "1") (pinfunction "1_1") (pintype "passive"))
      (node (ref "U2") (pin "24") (pinfunction "RBIAS_24") (pintype "bidirectional"))
    )
    (net (code "63") (name "Net-(U2-RESERVED_PU1)") (class "Default")
      (node (ref "R7") (pin "1") (pinfunction "1_1") (pintype "passive"))
      (node (ref "U2") (pin "20") (pinfunction "RESERVED_PU1_20") (pintype "bidirectional"))
    )
    (net (code "64") (name "Net-(U2-RESERVED_PU2)") (class "Default")
      (node (ref "R10") (pin "1") (pinfunction "1_1") (pintype "passive"))
      (node (ref "U2") (pin "21") (pinfunction "RESERVED_PU2_21") (pintype "bidirectional"))
    )
    (net (code "65") (name "Net-(U2-RX_DV{slash}MII_MODE)") (class "Default")
      (node (ref "R12") (pin "1") (pinfunction "1_1") (pintype "passive"))
      (node (ref "U2") (pin "39") (pinfunction "RX_DV/MII_MODE_39") (pintype "bidirectional"))
    )
    (net (code "66") (name "Net-(U2-TX+)") (class "Default")
      (node (ref "RN1") (pin "1") (pinfunction "1_1") (pintype "passive"))
      (node (ref "U2") (pin "17") (pinfunction "TX+_17") (pintype "bidirectional"))
      (node (ref "X3") (pin "1") (pinfunction "TD+_1") (pintype "passive"))
    )
    (net (code "67") (name "Net-(U3-BYPASS)") (class "Default")
      (node (ref "C5") (pin "1") (pinfunction "1_1") (pintype "passive"))
      (node (ref "U3") (pin "4") (pinfunction "BYPASS_4") (pintype "bidirectional"))
    )
    (net (code "68") (name "Net-(U3-INHIBIT)") (class "Default")
      (node (ref "C7") (pin "1") (pinfunction "1_1") (pintype "passive"))
      (node (ref "R4") (pin "1") (pinfunction "1_1") (pintype "passive"))
      (node (ref "U3") (pin "1") (pinfunction "VIN_1") (pintype "bidirectional"))
      (node (ref "U3") (pin "3") (pinfunction "INHIBIT_3") (pintype "bidirectional"))
    )
    (net (code "69") (name "Net-(U4-RS)") (class "Default")
      (node (ref "R1") (pin "1") (pinfunction "1_1") (pintype "passive"))
      (node (ref "U4") (pin "P$8") (pinfunction "RS_P$8") (pintype "bidirectional"))
    )
    (net (code "70") (name "unconnected-(U1A-PA0-Pad23)") (class "Default")
      (node (ref "U1") (pin "23") (pinfunction "PA0_23") (pintype "passive"))
    )
    (net (code "71") (name "unconnected-(U1A-PA3-Pad26)") (class "Default")
      (node (ref "U1") (pin "26") (pinfunction "PA3_26") (pintype "passive"))
    )
    (net (code "72") (name "unconnected-(U1A-PA4-Pad29)") (class "Default")
      (node (ref "U1") (pin "29") (pinfunction "PA4_29") (pintype "passive"))
    )
    (net (code "73") (name "unconnected-(U1A-PA5-Pad30)") (class "Default")
      (node (ref "U1") (pin "30") (pinfunction "PA5_30") (pintype "passive"))
    )
    (net (code "74") (name "unconnected-(U1A-PA6-Pad31)") (class "Default")
      (node (ref "U1") (pin "31") (pinfunction "PA6_31") (pintype "passive"))
    )
    (net (code "75") (name "unconnected-(U1A-PA8-Pad67)") (class "Default")
      (node (ref "U1") (pin "67") (pinfunction "PA8_67") (pintype "passive"))
    )
    (net (code "76") (name "unconnected-(U1A-PB0-Pad35)") (class "Default")
      (node (ref "U1") (pin "35") (pinfunction "PB0_35") (pintype "passive"))
    )
    (net (code "77") (name "unconnected-(U1A-PB1-Pad36)") (class "Default")
      (node (ref "U1") (pin "36") (pinfunction "PB1_36") (pintype "passive"))
    )
    (net (code "78") (name "unconnected-(U1A-PB2-Pad37)") (class "Default")
      (node (ref "U1") (pin "37") (pinfunction "PB2_37") (pintype "passive"))
    )
    (net (code "79") (name "unconnected-(U1A-PB4-Pad90)") (class "Default")
      (node (ref "U1") (pin "90") (pinfunction "PB4_90") (pintype "passive"))
    )
    (net (code "80") (name "unconnected-(U1A-PB5-Pad91)") (class "Default")
      (node (ref "U1") (pin "91") (pinfunction "PB5_91") (pintype "passive"))
    )
    (net (code "81") (name "unconnected-(U1A-PB10-Pad47)") (class "Default")
      (node (ref "U1") (pin "47") (pinfunction "PB10_47") (pintype "passive"))
    )
    (net (code "82") (name "unconnected-(U1A-PB14-Pad53)") (class "Default")
      (node (ref "U1") (pin "53") (pinfunction "PB14_53") (pintype "passive"))
    )
    (net (code "83") (name "unconnected-(U1A-PB15-Pad54)") (class "Default")
      (node (ref "U1") (pin "54") (pinfunction "PB15_54") (pintype "passive"))
    )
    (net (code "84") (name "unconnected-(U1A-PC0-Pad15)") (class "Default")
      (node (ref "U1") (pin "15") (pinfunction "PC0_15") (pintype "passive"))
    )
    (net (code "85") (name "unconnected-(U1A-PC2-Pad17)") (class "Default")
      (node (ref "U1") (pin "17") (pinfunction "PC2_17") (pintype "passive"))
    )
    (net (code "86") (name "unconnected-(U1A-PC6-Pad63)") (class "Default")
      (node (ref "U1") (pin "63") (pinfunction "PC6_63") (pintype "passive"))
    )
    (net (code "87") (name "unconnected-(U1A-PC7-Pad64)") (class "Default")
      (node (ref "U1") (pin "64") (pinfunction "PC7_64") (pintype "passive"))
    )
    (net (code "88") (name "unconnected-(U1A-PC8-Pad65)") (class "Default")
      (node (ref "U1") (pin "65") (pinfunction "PC8_65") (pintype "passive"))
    )
    (net (code "89") (name "unconnected-(U1A-PC9-Pad66)") (class "Default")
      (node (ref "U1") (pin "66") (pinfunction "PC9_66") (pintype "passive"))
    )
    (net (code "90") (name "unconnected-(U1A-PC12-Pad80)") (class "Default")
      (node (ref "U1") (pin "80") (pinfunction "PC12_80") (pintype "passive"))
    )
    (net (code "91") (name "unconnected-(U1A-PC13-Pad7)") (class "Default")
      (node (ref "U1") (pin "7") (pinfunction "PC13_7") (pintype "passive"))
    )
    (net (code "92") (name "unconnected-(U1A-PC14-Pad8)") (class "Default")
      (node (ref "U1") (pin "8") (pinfunction "PC14_8") (pintype "passive"))
    )
    (net (code "93") (name "unconnected-(U1A-PC15-Pad9)") (class "Default")
      (node (ref "U1") (pin "9") (pinfunction "PC15_9") (pintype "passive"))
    )
    (net (code "94") (name "unconnected-(U1A-PD2-Pad83)") (class "Default")
      (node (ref "U1") (pin "83") (pinfunction "PD2_83") (pintype "passive"))
    )
    (net (code "95") (name "unconnected-(U1A-PD3-Pad84)") (class "Default")
      (node (ref "U1") (pin "84") (pinfunction "PD3_84") (pintype "passive"))
    )
    (net (code "96") (name "unconnected-(U1A-PD4-Pad85)") (class "Default")
      (node (ref "U1") (pin "85") (pinfunction "PD4_85") (pintype "passive"))
    )
    (net (code "97") (name "unconnected-(U1A-PD5-Pad86)") (class "Default")
      (node (ref "U1") (pin "86") (pinfunction "PD5_86") (pintype "passive"))
    )
    (net (code "98") (name "unconnected-(U1A-PD6-Pad87)") (class "Default")
      (node (ref "U1") (pin "87") (pinfunction "PD6_87") (pintype "passive"))
    )
    (net (code "99") (name "unconnected-(U1A-PD7-Pad88)") (class "Default")
      (node (ref "U1") (pin "88") (pinfunction "PD7_88") (pintype "passive"))
    )
    (net (code "100") (name "unconnected-(U1A-PD8-Pad55)") (class "Default")
      (node (ref "U1") (pin "55") (pinfunction "PD8_55") (pintype "passive"))
    )
    (net (code "101") (name "unconnected-(U1A-PD9-Pad56)") (class "Default")
      (node (ref "U1") (pin "56") (pinfunction "PD9_56") (pintype "passive"))
    )
    (net (code "102") (name "unconnected-(U1A-PD10-Pad57)") (class "Default")
      (node (ref "U1") (pin "57") (pinfunction "PD10_57") (pintype "passive"))
    )
    (net (code "103") (name "unconnected-(U1A-PD11-Pad58)") (class "Default")
      (node (ref "U1") (pin "58") (pinfunction "PD11_58") (pintype "passive"))
    )
    (net (code "104") (name "unconnected-(U1A-PD12-Pad59)") (class "Default")
      (node (ref "U1") (pin "59") (pinfunction "PD12_59") (pintype "passive"))
    )
    (net (code "105") (name "unconnected-(U1A-PD13-Pad60)") (class "Default")
      (node (ref "U1") (pin "60") (pinfunction "PD13_60") (pintype "passive"))
    )
    (net (code "106") (name "unconnected-(U1A-PD14-Pad61)") (class "Default")
      (node (ref "U1") (pin "61") (pinfunction "PD14_61") (pintype "passive"))
    )
    (net (code "107") (name "unconnected-(U1A-PD15-Pad62)") (class "Default")
      (node (ref "U1") (pin "62") (pinfunction "PD15_62") (pintype "passive"))
    )
    (net (code "108") (name "unconnected-(U1A-PE0-Pad97)") (class "Default")
      (node (ref "U1") (pin "97") (pinfunction "PE0_97") (pintype "passive"))
    )
    (net (code "109") (name "unconnected-(U1A-PE1-Pad98)") (class "Default")
      (node (ref "U1") (pin "98") (pinfunction "PE1_98") (pintype "passive"))
    )
    (net (code "110") (name "unconnected-(U1A-PE2-Pad1)") (class "Default")
      (node (ref "U1") (pin "1") (pinfunction "PE2_1") (pintype "passive"))
    )
    (net (code "111") (name "unconnected-(U1A-PE3-Pad2)") (class "Default")
      (node (ref "U1") (pin "2") (pinfunction "PE3_2") (pintype "passive"))
    )
    (net (code "112") (name "unconnected-(U1A-PE4-Pad3)") (class "Default")
      (node (ref "U1") (pin "3") (pinfunction "PE4_3") (pintype "passive"))
    )
    (net (code "113") (name "unconnected-(U1A-PE5-Pad4)") (class "Default")
      (node (ref "U1") (pin "4") (pinfunction "PE5_4") (pintype "passive"))
    )
    (net (code "114") (name "unconnected-(U1A-PE6-Pad5)") (class "Default")
      (node (ref "U1") (pin "5") (pinfunction "PE6_5") (pintype "passive"))
    )
    (net (code "115") (name "unconnected-(U1A-PE7-Pad38)") (class "Default")
      (node (ref "U1") (pin "38") (pinfunction "PE7_38") (pintype "passive"))
    )
    (net (code "116") (name "unconnected-(U1A-PE8-Pad39)") (class "Default")
      (node (ref "U1") (pin "39") (pinfunction "PE8_39") (pintype "passive"))
    )
    (net (code "117") (name "unconnected-(U1A-PE9-Pad40)") (class "Default")
      (node (ref "U1") (pin "40") (pinfunction "PE9_40") (pintype "passive"))
    )
    (net (code "118") (name "unconnected-(U1A-PE10-Pad41)") (class "Default")
      (node (ref "U1") (pin "41") (pinfunction "PE10_41") (pintype "passive"))
    )
    (net (code "119") (name "unconnected-(U1A-PE11-Pad42)") (class "Default")
      (node (ref "U1") (pin "42") (pinfunction "PE11_42") (pintype "passive"))
    )
    (net (code "120") (name "unconnected-(U1A-PE12-Pad43)") (class "Default")
      (node (ref "U1") (pin "43") (pinfunction "PE12_43") (pintype "passive"))
    )
    (net (code "121") (name "unconnected-(U1A-PE13-Pad44)") (class "Default")
      (node (ref "U1") (pin "44") (pinfunction "PE13_44") (pintype "passive"))
    )
    (net (code "122") (name "unconnected-(U1A-PE14-Pad45)") (class "Default")
      (node (ref "U1") (pin "45") (pinfunction "PE14_45") (pintype "passive"))
    )
    (net (code "123") (name "unconnected-(U1A-PE15-Pad46)") (class "Default")
      (node (ref "U1") (pin "46") (pinfunction "PE15_46") (pintype "passive"))
    )
    (net (code "124") (name "unconnected-(U1A-PH1-Pad13)") (class "Default")
      (node (ref "U1") (pin "13") (pinfunction "PH1_13") (pintype "passive"))
    )
    (net (code "125") (name "unconnected-(U2-25MHZ_OUT-Pad25)") (class "Default")
      (node (ref "U2") (pin "25") (pinfunction "25MHZ_OUT_25") (pintype "bidirectional"))
    )
    (net (code "126") (name "unconnected-(U2-COL{slash}PHYAD0-Pad42)") (class "Default")
      (node (ref "U2") (pin "42") (pinfunction "COL/PHYAD0_42") (pintype "bidirectional"))
    )
    (net (code "127") (name "unconnected-(U2-RX_CLK-Pad38)") (class "Default")
      (node (ref "U2") (pin "38") (pinfunction "RX_CLK_38") (pintype "bidirectional"))
    )
    (net (code "128") (name "unconnected-(U2-RX_D2{slash}PHYAD3-Pad45)") (class "Default")
      (node (ref "U2") (pin "45") (pinfunction "RX_D2/PHYAD3_45") (pintype "bidirectional"))
    )
    (net (code "129") (name "unconnected-(U2-RX_D3{slash}PHYAD4-Pad46)") (class "Default")
      (node (ref "U2") (pin "46") (pinfunction "RX_D3/PHYAD4_46") (pintype "bidirectional"))
    )
    (net (code "130") (name "unconnected-(U2-RX_ER{slash}MDI_EN-Pad41)") (class "Default")
      (node (ref "U2") (pin "41") (pinfunction "RX_ER/MDI_EN_41") (pintype "bidirectional"))
    )
    (net (code "131") (name "unconnected-(U2-TX_CLK-Pad1)") (class "Default")
      (node (ref "U2") (pin "1") (pinfunction "TX_CLK_1") (pintype "bidirectional"))
    )
    (net (code "132") (name "unconnected-(U2-X2-Pad33)") (class "Default")
      (node (ref "U2") (pin "33") (pinfunction "X2_33") (pintype "bidirectional"))
    )
    (net (code "133") (name "unconnected-(U4-SHDN-PadP$5)") (class "Default")
      (node (ref "U4") (pin "P$5") (pinfunction "SHDN_P$5") (pintype "bidirectional"))
    )
    (net (code "134") (name "unconnected-(X6-Pad7)") (class "Default")
      (node (ref "X6") (pin "7") (pinfunction "7_7") (pintype "passive"))
    )
  )
)
